# SCH.net
KiCad netlist of a schematic drawn in EasyEDA
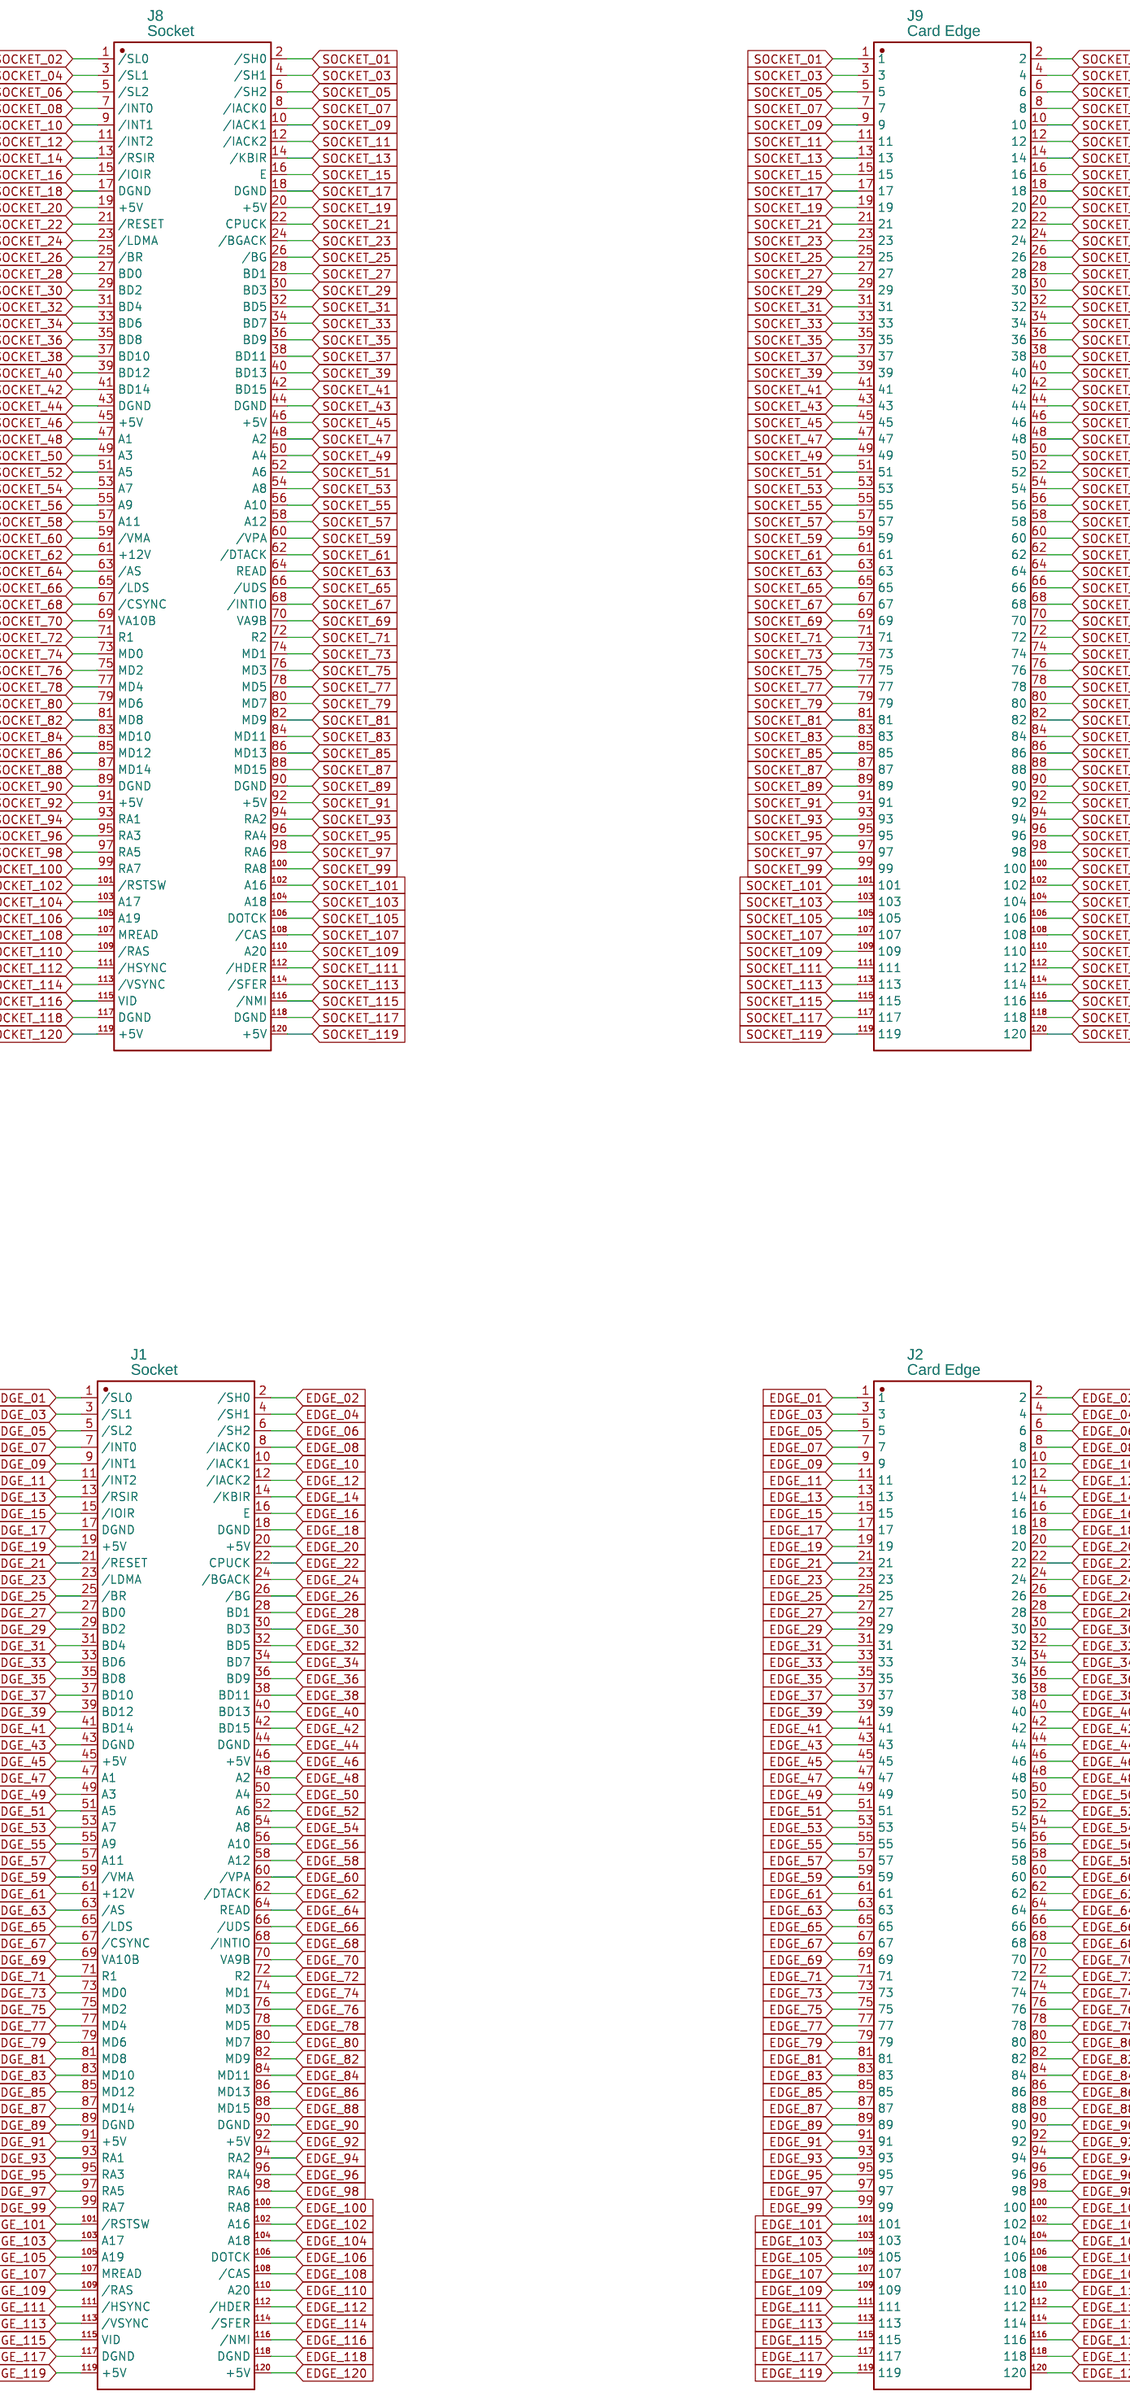
[diagram p0: schematic sheet]

(export (version "E")
  (design (tool "Eeschema 10.0.6"))
  (components
    (comp (ref "J1")
      (value "Socket")
      (fields
        (field (name "BOM_Manufacturer Part") "345-120-520-201")
        (field (name "BOM_Supplier Part") "587-345-120-520-201")
      )
      (libsource (lib "") (part "Apple Lisa 120-Pin Edge Connector_1"))
    )
    (comp (ref "J2")
      (value "Card Edge")
      (fields
        (field (name "BOM_Manufacturer Part") "345-120-520-201")
        (field (name "BOM_Supplier Part") "587-345-120-520-201")
      )
      (libsource (lib "") (part "Apple Lisa 120-Pin Edge Connector"))
    )
    (comp (ref "J8")
      (value "Socket")
      (fields
        (field (name "BOM_Manufacturer Part") "345-120-520-201")
        (field (name "BOM_Supplier Part") "587-345-120-520-201")
      )
      (libsource (lib "") (part "Apple Lisa 120-Pin Edge Connector_1"))
    )
    (comp (ref "J9")
      (value "Card Edge")
      (fields
        (field (name "BOM_Manufacturer Part") "345-120-520-201")
        (field (name "BOM_Supplier Part") "587-345-120-520-201")
      )
      (libsource (lib "") (part "Apple Lisa 120-Pin Edge Connector"))
    )
  )
  (nets
    (net (code "1") (name "EDGE_01") (class "Default")
      (node (ref "J1") (pin "1") (pinfunction "/SL0_1") (pintype "unspecified"))
      (node (ref "J2") (pin "1") (pinfunction "1_1") (pintype "unspecified"))
    )
    (net (code "2") (name "EDGE_02") (class "Default")
      (node (ref "J1") (pin "2") (pinfunction "/SH0_2") (pintype "unspecified"))
      (node (ref "J2") (pin "2") (pinfunction "2_2") (pintype "unspecified"))
    )
    (net (code "3") (name "EDGE_03") (class "Default")
      (node (ref "J1") (pin "3") (pinfunction "/SL1_3") (pintype "unspecified"))
      (node (ref "J2") (pin "3") (pinfunction "3_3") (pintype "unspecified"))
    )
    (net (code "4") (name "EDGE_04") (class "Default")
      (node (ref "J1") (pin "4") (pinfunction "/SH1_4") (pintype "unspecified"))
      (node (ref "J2") (pin "4") (pinfunction "4_4") (pintype "unspecified"))
    )
    (net (code "5") (name "EDGE_05") (class "Default")
      (node (ref "J1") (pin "5") (pinfunction "/SL2_5") (pintype "unspecified"))
      (node (ref "J2") (pin "5") (pinfunction "5_5") (pintype "unspecified"))
    )
    (net (code "6") (name "EDGE_06") (class "Default")
      (node (ref "J1") (pin "6") (pinfunction "/SH2_6") (pintype "unspecified"))
      (node (ref "J2") (pin "6") (pinfunction "6_6") (pintype "unspecified"))
    )
    (net (code "7") (name "EDGE_07") (class "Default")
      (node (ref "J1") (pin "7") (pinfunction "/INT0_7") (pintype "unspecified"))
      (node (ref "J2") (pin "7") (pinfunction "7_7") (pintype "unspecified"))
    )
    (net (code "8") (name "EDGE_08") (class "Default")
      (node (ref "J1") (pin "8") (pinfunction "/IACK0_8") (pintype "unspecified"))
      (node (ref "J2") (pin "8") (pinfunction "8_8") (pintype "unspecified"))
    )
    (net (code "9") (name "EDGE_09") (class "Default")
      (node (ref "J1") (pin "9") (pinfunction "/INT1_9") (pintype "unspecified"))
      (node (ref "J2") (pin "9") (pinfunction "9_9") (pintype "unspecified"))
    )
    (net (code "10") (name "EDGE_10") (class "Default")
      (node (ref "J1") (pin "10") (pinfunction "/IACK1_10") (pintype "unspecified"))
      (node (ref "J2") (pin "10") (pinfunction "10_10") (pintype "unspecified"))
    )
    (net (code "11") (name "EDGE_11") (class "Default")
      (node (ref "J1") (pin "11") (pinfunction "/INT2_11") (pintype "unspecified"))
      (node (ref "J2") (pin "11") (pinfunction "11_11") (pintype "unspecified"))
    )
    (net (code "12") (name "EDGE_12") (class "Default")
      (node (ref "J1") (pin "12") (pinfunction "/IACK2_12") (pintype "unspecified"))
      (node (ref "J2") (pin "12") (pinfunction "12_12") (pintype "unspecified"))
    )
    (net (code "13") (name "EDGE_13") (class "Default")
      (node (ref "J1") (pin "13") (pinfunction "/RSIR_13") (pintype "unspecified"))
      (node (ref "J2") (pin "13") (pinfunction "13_13") (pintype "unspecified"))
    )
    (net (code "14") (name "EDGE_14") (class "Default")
      (node (ref "J1") (pin "14") (pinfunction "/KBIR_14") (pintype "unspecified"))
      (node (ref "J2") (pin "14") (pinfunction "14_14") (pintype "unspecified"))
    )
    (net (code "15") (name "EDGE_15") (class "Default")
      (node (ref "J1") (pin "15") (pinfunction "/IOIR_15") (pintype "unspecified"))
      (node (ref "J2") (pin "15") (pinfunction "15_15") (pintype "unspecified"))
    )
    (net (code "16") (name "EDGE_16") (class "Default")
      (node (ref "J1") (pin "16") (pinfunction "E_16") (pintype "unspecified"))
      (node (ref "J2") (pin "16") (pinfunction "16_16") (pintype "unspecified"))
    )
    (net (code "17") (name "EDGE_17") (class "Default")
      (node (ref "J1") (pin "17") (pinfunction "DGND_17") (pintype "unspecified"))
      (node (ref "J2") (pin "17") (pinfunction "17_17") (pintype "unspecified"))
    )
    (net (code "18") (name "EDGE_18") (class "Default")
      (node (ref "J1") (pin "18") (pinfunction "DGND_18") (pintype "unspecified"))
      (node (ref "J2") (pin "18") (pinfunction "18_18") (pintype "unspecified"))
    )
    (net (code "19") (name "EDGE_19") (class "Default")
      (node (ref "J1") (pin "19") (pinfunction "+5V_19") (pintype "unspecified"))
      (node (ref "J2") (pin "19") (pinfunction "19_19") (pintype "unspecified"))
    )
    (net (code "20") (name "EDGE_20") (class "Default")
      (node (ref "J1") (pin "20") (pinfunction "+5V_20") (pintype "unspecified"))
      (node (ref "J2") (pin "20") (pinfunction "20_20") (pintype "unspecified"))
    )
    (net (code "21") (name "EDGE_21") (class "Default")
      (node (ref "J1") (pin "21") (pinfunction "/RESET_21") (pintype "unspecified"))
      (node (ref "J2") (pin "21") (pinfunction "21_21") (pintype "unspecified"))
    )
    (net (code "22") (name "EDGE_22") (class "Default")
      (node (ref "J1") (pin "22") (pinfunction "CPUCK_22") (pintype "unspecified"))
      (node (ref "J2") (pin "22") (pinfunction "22_22") (pintype "unspecified"))
    )
    (net (code "23") (name "EDGE_23") (class "Default")
      (node (ref "J1") (pin "23") (pinfunction "/LDMA_23") (pintype "unspecified"))
      (node (ref "J2") (pin "23") (pinfunction "23_23") (pintype "unspecified"))
    )
    (net (code "24") (name "EDGE_24") (class "Default")
      (node (ref "J1") (pin "24") (pinfunction "/BGACK_24") (pintype "unspecified"))
      (node (ref "J2") (pin "24") (pinfunction "24_24") (pintype "unspecified"))
    )
    (net (code "25") (name "EDGE_25") (class "Default")
      (node (ref "J1") (pin "25") (pinfunction "/BR_25") (pintype "unspecified"))
      (node (ref "J2") (pin "25") (pinfunction "25_25") (pintype "unspecified"))
    )
    (net (code "26") (name "EDGE_26") (class "Default")
      (node (ref "J1") (pin "26") (pinfunction "/BG_26") (pintype "unspecified"))
      (node (ref "J2") (pin "26") (pinfunction "26_26") (pintype "unspecified"))
    )
    (net (code "27") (name "EDGE_27") (class "Default")
      (node (ref "J1") (pin "27") (pinfunction "BD0_27") (pintype "unspecified"))
      (node (ref "J2") (pin "27") (pinfunction "27_27") (pintype "unspecified"))
    )
    (net (code "28") (name "EDGE_28") (class "Default")
      (node (ref "J1") (pin "28") (pinfunction "BD1_28") (pintype "unspecified"))
      (node (ref "J2") (pin "28") (pinfunction "28_28") (pintype "unspecified"))
    )
    (net (code "29") (name "EDGE_29") (class "Default")
      (node (ref "J1") (pin "29") (pinfunction "BD2_29") (pintype "unspecified"))
      (node (ref "J2") (pin "29") (pinfunction "29_29") (pintype "unspecified"))
    )
    (net (code "30") (name "EDGE_30") (class "Default")
      (node (ref "J1") (pin "30") (pinfunction "BD3_30") (pintype "unspecified"))
      (node (ref "J2") (pin "30") (pinfunction "30_30") (pintype "unspecified"))
    )
    (net (code "31") (name "EDGE_31") (class "Default")
      (node (ref "J1") (pin "31") (pinfunction "BD4_31") (pintype "unspecified"))
      (node (ref "J2") (pin "31") (pinfunction "31_31") (pintype "unspecified"))
    )
    (net (code "32") (name "EDGE_32") (class "Default")
      (node (ref "J1") (pin "32") (pinfunction "BD5_32") (pintype "unspecified"))
      (node (ref "J2") (pin "32") (pinfunction "32_32") (pintype "unspecified"))
    )
    (net (code "33") (name "EDGE_33") (class "Default")
      (node (ref "J1") (pin "33") (pinfunction "BD6_33") (pintype "unspecified"))
      (node (ref "J2") (pin "33") (pinfunction "33_33") (pintype "unspecified"))
    )
    (net (code "34") (name "EDGE_34") (class "Default")
      (node (ref "J1") (pin "34") (pinfunction "BD7_34") (pintype "unspecified"))
      (node (ref "J2") (pin "34") (pinfunction "34_34") (pintype "unspecified"))
    )
    (net (code "35") (name "EDGE_35") (class "Default")
      (node (ref "J1") (pin "35") (pinfunction "BD8_35") (pintype "unspecified"))
      (node (ref "J2") (pin "35") (pinfunction "35_35") (pintype "unspecified"))
    )
    (net (code "36") (name "EDGE_36") (class "Default")
      (node (ref "J1") (pin "36") (pinfunction "BD9_36") (pintype "unspecified"))
      (node (ref "J2") (pin "36") (pinfunction "36_36") (pintype "unspecified"))
    )
    (net (code "37") (name "EDGE_37") (class "Default")
      (node (ref "J1") (pin "37") (pinfunction "BD10_37") (pintype "unspecified"))
      (node (ref "J2") (pin "37") (pinfunction "37_37") (pintype "unspecified"))
    )
    (net (code "38") (name "EDGE_38") (class "Default")
      (node (ref "J1") (pin "38") (pinfunction "BD11_38") (pintype "unspecified"))
      (node (ref "J2") (pin "38") (pinfunction "38_38") (pintype "unspecified"))
    )
    (net (code "39") (name "EDGE_39") (class "Default")
      (node (ref "J1") (pin "39") (pinfunction "BD12_39") (pintype "unspecified"))
      (node (ref "J2") (pin "39") (pinfunction "39_39") (pintype "unspecified"))
    )
    (net (code "40") (name "EDGE_40") (class "Default")
      (node (ref "J1") (pin "40") (pinfunction "BD13_40") (pintype "unspecified"))
      (node (ref "J2") (pin "40") (pinfunction "40_40") (pintype "unspecified"))
    )
    (net (code "41") (name "EDGE_41") (class "Default")
      (node (ref "J1") (pin "41") (pinfunction "BD14_41") (pintype "unspecified"))
      (node (ref "J2") (pin "41") (pinfunction "41_41") (pintype "unspecified"))
    )
    (net (code "42") (name "EDGE_42") (class "Default")
      (node (ref "J1") (pin "42") (pinfunction "BD15_42") (pintype "unspecified"))
      (node (ref "J2") (pin "42") (pinfunction "42_42") (pintype "unspecified"))
    )
    (net (code "43") (name "EDGE_43") (class "Default")
      (node (ref "J1") (pin "43") (pinfunction "DGND_43") (pintype "unspecified"))
      (node (ref "J2") (pin "43") (pinfunction "43_43") (pintype "unspecified"))
    )
    (net (code "44") (name "EDGE_44") (class "Default")
      (node (ref "J1") (pin "44") (pinfunction "DGND_44") (pintype "unspecified"))
      (node (ref "J2") (pin "44") (pinfunction "44_44") (pintype "unspecified"))
    )
    (net (code "45") (name "EDGE_45") (class "Default")
      (node (ref "J1") (pin "45") (pinfunction "+5V_45") (pintype "unspecified"))
      (node (ref "J2") (pin "45") (pinfunction "45_45") (pintype "unspecified"))
    )
    (net (code "46") (name "EDGE_46") (class "Default")
      (node (ref "J1") (pin "46") (pinfunction "+5V_46") (pintype "unspecified"))
      (node (ref "J2") (pin "46") (pinfunction "46_46") (pintype "unspecified"))
    )
    (net (code "47") (name "EDGE_47") (class "Default")
      (node (ref "J1") (pin "47") (pinfunction "A1_47") (pintype "unspecified"))
      (node (ref "J2") (pin "47") (pinfunction "47_47") (pintype "unspecified"))
    )
    (net (code "48") (name "EDGE_48") (class "Default")
      (node (ref "J1") (pin "48") (pinfunction "A2_48") (pintype "unspecified"))
      (node (ref "J2") (pin "48") (pinfunction "48_48") (pintype "unspecified"))
    )
    (net (code "49") (name "EDGE_49") (class "Default")
      (node (ref "J1") (pin "49") (pinfunction "A3_49") (pintype "unspecified"))
      (node (ref "J2") (pin "49") (pinfunction "49_49") (pintype "unspecified"))
    )
    (net (code "50") (name "EDGE_50") (class "Default")
      (node (ref "J1") (pin "50") (pinfunction "A4_50") (pintype "unspecified"))
      (node (ref "J2") (pin "50") (pinfunction "50_50") (pintype "unspecified"))
    )
    (net (code "51") (name "EDGE_51") (class "Default")
      (node (ref "J1") (pin "51") (pinfunction "A5_51") (pintype "unspecified"))
      (node (ref "J2") (pin "51") (pinfunction "51_51") (pintype "unspecified"))
    )
    (net (code "52") (name "EDGE_52") (class "Default")
      (node (ref "J1") (pin "52") (pinfunction "A6_52") (pintype "unspecified"))
      (node (ref "J2") (pin "52") (pinfunction "52_52") (pintype "unspecified"))
    )
    (net (code "53") (name "EDGE_53") (class "Default")
      (node (ref "J1") (pin "53") (pinfunction "A7_53") (pintype "unspecified"))
      (node (ref "J2") (pin "53") (pinfunction "53_53") (pintype "unspecified"))
    )
    (net (code "54") (name "EDGE_54") (class "Default")
      (node (ref "J1") (pin "54") (pinfunction "A8_54") (pintype "unspecified"))
      (node (ref "J2") (pin "54") (pinfunction "54_54") (pintype "unspecified"))
    )
    (net (code "55") (name "EDGE_55") (class "Default")
      (node (ref "J1") (pin "55") (pinfunction "A9_55") (pintype "unspecified"))
      (node (ref "J2") (pin "55") (pinfunction "55_55") (pintype "unspecified"))
    )
    (net (code "56") (name "EDGE_56") (class "Default")
      (node (ref "J1") (pin "56") (pinfunction "A10_56") (pintype "unspecified"))
      (node (ref "J2") (pin "56") (pinfunction "56_56") (pintype "unspecified"))
    )
    (net (code "57") (name "EDGE_57") (class "Default")
      (node (ref "J1") (pin "57") (pinfunction "A11_57") (pintype "unspecified"))
      (node (ref "J2") (pin "57") (pinfunction "57_57") (pintype "unspecified"))
    )
    (net (code "58") (name "EDGE_58") (class "Default")
      (node (ref "J1") (pin "58") (pinfunction "A12_58") (pintype "unspecified"))
      (node (ref "J2") (pin "58") (pinfunction "58_58") (pintype "unspecified"))
    )
    (net (code "59") (name "EDGE_59") (class "Default")
      (node (ref "J1") (pin "59") (pinfunction "/VMA_59") (pintype "unspecified"))
      (node (ref "J2") (pin "59") (pinfunction "59_59") (pintype "unspecified"))
    )
    (net (code "60") (name "EDGE_60") (class "Default")
      (node (ref "J1") (pin "60") (pinfunction "/VPA_60") (pintype "unspecified"))
      (node (ref "J2") (pin "60") (pinfunction "60_60") (pintype "unspecified"))
    )
    (net (code "61") (name "EDGE_61") (class "Default")
      (node (ref "J1") (pin "61") (pinfunction "+12V_61") (pintype "unspecified"))
      (node (ref "J2") (pin "61") (pinfunction "61_61") (pintype "unspecified"))
    )
    (net (code "62") (name "EDGE_62") (class "Default")
      (node (ref "J1") (pin "62") (pinfunction "/DTACK_62") (pintype "unspecified"))
      (node (ref "J2") (pin "62") (pinfunction "62_62") (pintype "unspecified"))
    )
    (net (code "63") (name "EDGE_63") (class "Default")
      (node (ref "J1") (pin "63") (pinfunction "/AS_63") (pintype "unspecified"))
      (node (ref "J2") (pin "63") (pinfunction "63_63") (pintype "unspecified"))
    )
    (net (code "64") (name "EDGE_64") (class "Default")
      (node (ref "J1") (pin "64") (pinfunction "READ_64") (pintype "unspecified"))
      (node (ref "J2") (pin "64") (pinfunction "64_64") (pintype "unspecified"))
    )
    (net (code "65") (name "EDGE_65") (class "Default")
      (node (ref "J1") (pin "65") (pinfunction "/LDS_65") (pintype "unspecified"))
      (node (ref "J2") (pin "65") (pinfunction "65_65") (pintype "unspecified"))
    )
    (net (code "66") (name "EDGE_66") (class "Default")
      (node (ref "J1") (pin "66") (pinfunction "/UDS_66") (pintype "unspecified"))
      (node (ref "J2") (pin "66") (pinfunction "66_66") (pintype "unspecified"))
    )
    (net (code "67") (name "EDGE_67") (class "Default")
      (node (ref "J1") (pin "67") (pinfunction "/CSYNC_67") (pintype "unspecified"))
      (node (ref "J2") (pin "67") (pinfunction "67_67") (pintype "unspecified"))
    )
    (net (code "68") (name "EDGE_68") (class "Default")
      (node (ref "J1") (pin "68") (pinfunction "/INTIO_68") (pintype "unspecified"))
      (node (ref "J2") (pin "68") (pinfunction "68_68") (pintype "unspecified"))
    )
    (net (code "69") (name "EDGE_69") (class "Default")
      (node (ref "J1") (pin "69") (pinfunction "VA10B_69") (pintype "unspecified"))
      (node (ref "J2") (pin "69") (pinfunction "69_69") (pintype "unspecified"))
    )
    (net (code "70") (name "EDGE_70") (class "Default")
      (node (ref "J1") (pin "70") (pinfunction "VA9B_70") (pintype "unspecified"))
      (node (ref "J2") (pin "70") (pinfunction "70_70") (pintype "unspecified"))
    )
    (net (code "71") (name "EDGE_71") (class "Default")
      (node (ref "J1") (pin "71") (pinfunction "R1_71") (pintype "unspecified"))
      (node (ref "J2") (pin "71") (pinfunction "71_71") (pintype "unspecified"))
    )
    (net (code "72") (name "EDGE_72") (class "Default")
      (node (ref "J1") (pin "72") (pinfunction "R2_72") (pintype "unspecified"))
      (node (ref "J2") (pin "72") (pinfunction "72_72") (pintype "unspecified"))
    )
    (net (code "73") (name "EDGE_73") (class "Default")
      (node (ref "J1") (pin "73") (pinfunction "MD0_73") (pintype "unspecified"))
      (node (ref "J2") (pin "73") (pinfunction "73_73") (pintype "unspecified"))
    )
    (net (code "74") (name "EDGE_74") (class "Default")
      (node (ref "J1") (pin "74") (pinfunction "MD1_74") (pintype "unspecified"))
      (node (ref "J2") (pin "74") (pinfunction "74_74") (pintype "unspecified"))
    )
    (net (code "75") (name "EDGE_75") (class "Default")
      (node (ref "J1") (pin "75") (pinfunction "MD2_75") (pintype "unspecified"))
      (node (ref "J2") (pin "75") (pinfunction "75_75") (pintype "unspecified"))
    )
    (net (code "76") (name "EDGE_76") (class "Default")
      (node (ref "J1") (pin "76") (pinfunction "MD3_76") (pintype "unspecified"))
      (node (ref "J2") (pin "76") (pinfunction "76_76") (pintype "unspecified"))
    )
    (net (code "77") (name "EDGE_77") (class "Default")
      (node (ref "J1") (pin "77") (pinfunction "MD4_77") (pintype "unspecified"))
      (node (ref "J2") (pin "77") (pinfunction "77_77") (pintype "unspecified"))
    )
    (net (code "78") (name "EDGE_78") (class "Default")
      (node (ref "J1") (pin "78") (pinfunction "MD5_78") (pintype "unspecified"))
      (node (ref "J2") (pin "78") (pinfunction "78_78") (pintype "unspecified"))
    )
    (net (code "79") (name "EDGE_79") (class "Default")
      (node (ref "J1") (pin "79") (pinfunction "MD6_79") (pintype "unspecified"))
      (node (ref "J2") (pin "79") (pinfunction "79_79") (pintype "unspecified"))
    )
    (net (code "80") (name "EDGE_80") (class "Default")
      (node (ref "J1") (pin "80") (pinfunction "MD7_80") (pintype "unspecified"))
      (node (ref "J2") (pin "80") (pinfunction "80_80") (pintype "unspecified"))
    )
    (net (code "81") (name "EDGE_81") (class "Default")
      (node (ref "J1") (pin "81") (pinfunction "MD8_81") (pintype "unspecified"))
      (node (ref "J2") (pin "81") (pinfunction "81_81") (pintype "unspecified"))
    )
    (net (code "82") (name "EDGE_82") (class "Default")
      (node (ref "J1") (pin "82") (pinfunction "MD9_82") (pintype "unspecified"))
      (node (ref "J2") (pin "82") (pinfunction "82_82") (pintype "unspecified"))
    )
    (net (code "83") (name "EDGE_83") (class "Default")
      (node (ref "J1") (pin "83") (pinfunction "MD10_83") (pintype "unspecified"))
      (node (ref "J2") (pin "83") (pinfunction "83_83") (pintype "unspecified"))
    )
    (net (code "84") (name "EDGE_84") (class "Default")
      (node (ref "J1") (pin "84") (pinfunction "MD11_84") (pintype "unspecified"))
      (node (ref "J2") (pin "84") (pinfunction "84_84") (pintype "unspecified"))
    )
    (net (code "85") (name "EDGE_85") (class "Default")
      (node (ref "J1") (pin "85") (pinfunction "MD12_85") (pintype "unspecified"))
      (node (ref "J2") (pin "85") (pinfunction "85_85") (pintype "unspecified"))
    )
    (net (code "86") (name "EDGE_86") (class "Default")
      (node (ref "J1") (pin "86") (pinfunction "MD13_86") (pintype "unspecified"))
      (node (ref "J2") (pin "86") (pinfunction "86_86") (pintype "unspecified"))
    )
    (net (code "87") (name "EDGE_87") (class "Default")
      (node (ref "J1") (pin "87") (pinfunction "MD14_87") (pintype "unspecified"))
      (node (ref "J2") (pin "87") (pinfunction "87_87") (pintype "unspecified"))
    )
    (net (code "88") (name "EDGE_88") (class "Default")
      (node (ref "J1") (pin "88") (pinfunction "MD15_88") (pintype "unspecified"))
      (node (ref "J2") (pin "88") (pinfunction "88_88") (pintype "unspecified"))
    )
    (net (code "89") (name "EDGE_89") (class "Default")
      (node (ref "J1") (pin "89") (pinfunction "DGND_89") (pintype "unspecified"))
      (node (ref "J2") (pin "89") (pinfunction "89_89") (pintype "unspecified"))
    )
    (net (code "90") (name "EDGE_90") (class "Default")
      (node (ref "J1") (pin "90") (pinfunction "DGND_90") (pintype "unspecified"))
      (node (ref "J2") (pin "90") (pinfunction "90_90") (pintype "unspecified"))
    )
    (net (code "91") (name "EDGE_91") (class "Default")
      (node (ref "J1") (pin "91") (pinfunction "+5V_91") (pintype "unspecified"))
      (node (ref "J2") (pin "91") (pinfunction "91_91") (pintype "unspecified"))
    )
    (net (code "92") (name "EDGE_92") (class "Default")
      (node (ref "J1") (pin "92") (pinfunction "+5V_92") (pintype "unspecified"))
      (node (ref "J2") (pin "92") (pinfunction "92_92") (pintype "unspecified"))
    )
    (net (code "93") (name "EDGE_93") (class "Default")
      (node (ref "J1") (pin "93") (pinfunction "RA1_93") (pintype "unspecified"))
      (node (ref "J2") (pin "93") (pinfunction "93_93") (pintype "unspecified"))
    )
    (net (code "94") (name "EDGE_94") (class "Default")
      (node (ref "J1") (pin "94") (pinfunction "RA2_94") (pintype "unspecified"))
      (node (ref "J2") (pin "94") (pinfunction "94_94") (pintype "unspecified"))
    )
    (net (code "95") (name "EDGE_95") (class "Default")
      (node (ref "J1") (pin "95") (pinfunction "RA3_95") (pintype "unspecified"))
      (node (ref "J2") (pin "95") (pinfunction "95_95") (pintype "unspecified"))
    )
    (net (code "96") (name "EDGE_96") (class "Default")
      (node (ref "J1") (pin "96") (pinfunction "RA4_96") (pintype "unspecified"))
      (node (ref "J2") (pin "96") (pinfunction "96_96") (pintype "unspecified"))
    )
    (net (code "97") (name "EDGE_97") (class "Default")
      (node (ref "J1") (pin "97") (pinfunction "RA5_97") (pintype "unspecified"))
      (node (ref "J2") (pin "97") (pinfunction "97_97") (pintype "unspecified"))
    )
    (net (code "98") (name "EDGE_98") (class "Default")
      (node (ref "J1") (pin "98") (pinfunction "RA6_98") (pintype "unspecified"))
      (node (ref "J2") (pin "98") (pinfunction "98_98") (pintype "unspecified"))
    )
    (net (code "99") (name "EDGE_99") (class "Default")
      (node (ref "J1") (pin "99") (pinfunction "RA7_99") (pintype "unspecified"))
      (node (ref "J2") (pin "99") (pinfunction "99_99") (pintype "unspecified"))
    )
    (net (code "100") (name "EDGE_100") (class "Default")
      (node (ref "J1") (pin "100") (pinfunction "RA8_100") (pintype "unspecified"))
      (node (ref "J2") (pin "100") (pinfunction "100_100") (pintype "unspecified"))
    )
    (net (code "101") (name "EDGE_101") (class "Default")
      (node (ref "J1") (pin "101") (pinfunction "/RSTSW_101") (pintype "unspecified"))
      (node (ref "J2") (pin "101") (pinfunction "101_101") (pintype "unspecified"))
    )
    (net (code "102") (name "EDGE_102") (class "Default")
      (node (ref "J1") (pin "102") (pinfunction "A16_102") (pintype "unspecified"))
      (node (ref "J2") (pin "102") (pinfunction "102_102") (pintype "unspecified"))
    )
    (net (code "103") (name "EDGE_103") (class "Default")
      (node (ref "J1") (pin "103") (pinfunction "A17_103") (pintype "unspecified"))
      (node (ref "J2") (pin "103") (pinfunction "103_103") (pintype "unspecified"))
    )
    (net (code "104") (name "EDGE_104") (class "Default")
      (node (ref "J1") (pin "104") (pinfunction "A18_104") (pintype "unspecified"))
      (node (ref "J2") (pin "104") (pinfunction "104_104") (pintype "unspecified"))
    )
    (net (code "105") (name "EDGE_105") (class "Default")
      (node (ref "J1") (pin "105") (pinfunction "A19_105") (pintype "unspecified"))
      (node (ref "J2") (pin "105") (pinfunction "105_105") (pintype "unspecified"))
    )
    (net (code "106") (name "EDGE_106") (class "Default")
      (node (ref "J1") (pin "106") (pinfunction "DOTCK_106") (pintype "unspecified"))
      (node (ref "J2") (pin "106") (pinfunction "106_106") (pintype "unspecified"))
    )
    (net (code "107") (name "EDGE_107") (class "Default")
      (node (ref "J1") (pin "107") (pinfunction "MREAD_107") (pintype "unspecified"))
      (node (ref "J2") (pin "107") (pinfunction "107_107") (pintype "unspecified"))
    )
    (net (code "108") (name "EDGE_108") (class "Default")
      (node (ref "J1") (pin "108") (pinfunction "/CAS_108") (pintype "unspecified"))
      (node (ref "J2") (pin "108") (pinfunction "108_108") (pintype "unspecified"))
    )
    (net (code "109") (name "EDGE_109") (class "Default")
      (node (ref "J1") (pin "109") (pinfunction "/RAS_109") (pintype "unspecified"))
      (node (ref "J2") (pin "109") (pinfunction "109_109") (pintype "unspecified"))
    )
    (net (code "110") (name "EDGE_110") (class "Default")
      (node (ref "J1") (pin "110") (pinfunction "A20_110") (pintype "unspecified"))
      (node (ref "J2") (pin "110") (pinfunction "110_110") (pintype "unspecified"))
    )
    (net (code "111") (name "EDGE_111") (class "Default")
      (node (ref "J1") (pin "111") (pinfunction "/HSYNC_111") (pintype "unspecified"))
      (node (ref "J2") (pin "111") (pinfunction "111_111") (pintype "unspecified"))
    )
    (net (code "112") (name "EDGE_112") (class "Default")
      (node (ref "J1") (pin "112") (pinfunction "/HDER_112") (pintype "unspecified"))
      (node (ref "J2") (pin "112") (pinfunction "112_112") (pintype "unspecified"))
    )
    (net (code "113") (name "EDGE_113") (class "Default")
      (node (ref "J1") (pin "113") (pinfunction "/VSYNC_113") (pintype "unspecified"))
      (node (ref "J2") (pin "113") (pinfunction "113_113") (pintype "unspecified"))
    )
    (net (code "114") (name "EDGE_114") (class "Default")
      (node (ref "J1") (pin "114") (pinfunction "/SFER_114") (pintype "unspecified"))
      (node (ref "J2") (pin "114") (pinfunction "114_114") (pintype "unspecified"))
    )
    (net (code "115") (name "EDGE_115") (class "Default")
      (node (ref "J1") (pin "115") (pinfunction "VID_115") (pintype "unspecified"))
      (node (ref "J2") (pin "115") (pinfunction "115_115") (pintype "unspecified"))
    )
    (net (code "116") (name "EDGE_116") (class "Default")
      (node (ref "J1") (pin "116") (pinfunction "/NMI_116") (pintype "unspecified"))
      (node (ref "J2") (pin "116") (pinfunction "116_116") (pintype "unspecified"))
    )
    (net (code "117") (name "EDGE_117") (class "Default")
      (node (ref "J1") (pin "117") (pinfunction "DGND_117") (pintype "unspecified"))
      (node (ref "J2") (pin "117") (pinfunction "117_117") (pintype "unspecified"))
    )
    (net (code "118") (name "EDGE_118") (class "Default")
      (node (ref "J1") (pin "118") (pinfunction "DGND_118") (pintype "unspecified"))
      (node (ref "J2") (pin "118") (pinfunction "118_118") (pintype "unspecified"))
    )
    (net (code "119") (name "EDGE_119") (class "Default")
      (node (ref "J1") (pin "119") (pinfunction "+5V_119") (pintype "unspecified"))
      (node (ref "J2") (pin "119") (pinfunction "119_119") (pintype "unspecified"))
    )
    (net (code "120") (name "EDGE_120") (class "Default")
      (node (ref "J1") (pin "120") (pinfunction "+5V_120") (pintype "unspecified"))
      (node (ref "J2") (pin "120") (pinfunction "120_120") (pintype "unspecified"))
    )
    (net (code "121") (name "SOCKET_01") (class "Default")
      (node (ref "J8") (pin "2") (pinfunction "/SH0_2") (pintype "unspecified"))
      (node (ref "J9") (pin "1") (pinfunction "1_1") (pintype "unspecified"))
    )
    (net (code "122") (name "SOCKET_02") (class "Default")
      (node (ref "J8") (pin "1") (pinfunction "/SL0_1") (pintype "unspecified"))
      (node (ref "J9") (pin "2") (pinfunction "2_2") (pintype "unspecified"))
    )
    (net (code "123") (name "SOCKET_03") (class "Default")
      (node (ref "J8") (pin "4") (pinfunction "/SH1_4") (pintype "unspecified"))
      (node (ref "J9") (pin "3") (pinfunction "3_3") (pintype "unspecified"))
    )
    (net (code "124") (name "SOCKET_04") (class "Default")
      (node (ref "J8") (pin "3") (pinfunction "/SL1_3") (pintype "unspecified"))
      (node (ref "J9") (pin "4") (pinfunction "4_4") (pintype "unspecified"))
    )
    (net (code "125") (name "SOCKET_05") (class "Default")
      (node (ref "J8") (pin "6") (pinfunction "/SH2_6") (pintype "unspecified"))
      (node (ref "J9") (pin "5") (pinfunction "5_5") (pintype "unspecified"))
    )
    (net (code "126") (name "SOCKET_06") (class "Default")
      (node (ref "J8") (pin "5") (pinfunction "/SL2_5") (pintype "unspecified"))
      (node (ref "J9") (pin "6") (pinfunction "6_6") (pintype "unspecified"))
    )
    (net (code "127") (name "SOCKET_07") (class "Default")
      (node (ref "J8") (pin "8") (pinfunction "/IACK0_8") (pintype "unspecified"))
      (node (ref "J9") (pin "7") (pinfunction "7_7") (pintype "unspecified"))
    )
    (net (code "128") (name "SOCKET_08") (class "Default")
      (node (ref "J8") (pin "7") (pinfunction "/INT0_7") (pintype "unspecified"))
      (node (ref "J9") (pin "8") (pinfunction "8_8") (pintype "unspecified"))
    )
    (net (code "129") (name "SOCKET_09") (class "Default")
      (node (ref "J8") (pin "10") (pinfunction "/IACK1_10") (pintype "unspecified"))
      (node (ref "J9") (pin "9") (pinfunction "9_9") (pintype "unspecified"))
    )
    (net (code "130") (name "SOCKET_10") (class "Default")
      (node (ref "J8") (pin "9") (pinfunction "/INT1_9") (pintype "unspecified"))
      (node (ref "J9") (pin "10") (pinfunction "10_10") (pintype "unspecified"))
    )
    (net (code "131") (name "SOCKET_11") (class "Default")
      (node (ref "J8") (pin "12") (pinfunction "/IACK2_12") (pintype "unspecified"))
      (node (ref "J9") (pin "11") (pinfunction "11_11") (pintype "unspecified"))
    )
    (net (code "132") (name "SOCKET_12") (class "Default")
      (node (ref "J8") (pin "11") (pinfunction "/INT2_11") (pintype "unspecified"))
      (node (ref "J9") (pin "12") (pinfunction "12_12") (pintype "unspecified"))
    )
    (net (code "133") (name "SOCKET_13") (class "Default")
      (node (ref "J8") (pin "14") (pinfunction "/KBIR_14") (pintype "unspecified"))
      (node (ref "J9") (pin "13") (pinfunction "13_13") (pintype "unspecified"))
    )
    (net (code "134") (name "SOCKET_14") (class "Default")
      (node (ref "J8") (pin "13") (pinfunction "/RSIR_13") (pintype "unspecified"))
      (node (ref "J9") (pin "14") (pinfunction "14_14") (pintype "unspecified"))
    )
    (net (code "135") (name "SOCKET_15") (class "Default")
      (node (ref "J8") (pin "16") (pinfunction "E_16") (pintype "unspecified"))
      (node (ref "J9") (pin "15") (pinfunction "15_15") (pintype "unspecified"))
    )
    (net (code "136") (name "SOCKET_16") (class "Default")
      (node (ref "J8") (pin "15") (pinfunction "/IOIR_15") (pintype "unspecified"))
      (node (ref "J9") (pin "16") (pinfunction "16_16") (pintype "unspecified"))
    )
    (net (code "137") (name "SOCKET_17") (class "Default")
      (node (ref "J8") (pin "18") (pinfunction "DGND_18") (pintype "unspecified"))
      (node (ref "J9") (pin "17") (pinfunction "17_17") (pintype "unspecified"))
    )
    (net (code "138") (name "SOCKET_18") (class "Default")
      (node (ref "J8") (pin "17") (pinfunction "DGND_17") (pintype "unspecified"))
      (node (ref "J9") (pin "18") (pinfunction "18_18") (pintype "unspecified"))
    )
    (net (code "139") (name "SOCKET_19") (class "Default")
      (node (ref "J8") (pin "20") (pinfunction "+5V_20") (pintype "unspecified"))
      (node (ref "J9") (pin "19") (pinfunction "19_19") (pintype "unspecified"))
    )
    (net (code "140") (name "SOCKET_20") (class "Default")
      (node (ref "J8") (pin "19") (pinfunction "+5V_19") (pintype "unspecified"))
      (node (ref "J9") (pin "20") (pinfunction "20_20") (pintype "unspecified"))
    )
    (net (code "141") (name "SOCKET_21") (class "Default")
      (node (ref "J8") (pin "22") (pinfunction "CPUCK_22") (pintype "unspecified"))
      (node (ref "J9") (pin "21") (pinfunction "21_21") (pintype "unspecified"))
    )
    (net (code "142") (name "SOCKET_22") (class "Default")
      (node (ref "J8") (pin "21") (pinfunction "/RESET_21") (pintype "unspecified"))
      (node (ref "J9") (pin "22") (pinfunction "22_22") (pintype "unspecified"))
    )
    (net (code "143") (name "SOCKET_23") (class "Default")
      (node (ref "J8") (pin "24") (pinfunction "/BGACK_24") (pintype "unspecified"))
      (node (ref "J9") (pin "23") (pinfunction "23_23") (pintype "unspecified"))
    )
    (net (code "144") (name "SOCKET_24") (class "Default")
      (node (ref "J8") (pin "23") (pinfunction "/LDMA_23") (pintype "unspecified"))
      (node (ref "J9") (pin "24") (pinfunction "24_24") (pintype "unspecified"))
    )
    (net (code "145") (name "SOCKET_25") (class "Default")
      (node (ref "J8") (pin "26") (pinfunction "/BG_26") (pintype "unspecified"))
      (node (ref "J9") (pin "25") (pinfunction "25_25") (pintype "unspecified"))
    )
    (net (code "146") (name "SOCKET_26") (class "Default")
      (node (ref "J8") (pin "25") (pinfunction "/BR_25") (pintype "unspecified"))
      (node (ref "J9") (pin "26") (pinfunction "26_26") (pintype "unspecified"))
    )
    (net (code "147") (name "SOCKET_27") (class "Default")
      (node (ref "J8") (pin "28") (pinfunction "BD1_28") (pintype "unspecified"))
      (node (ref "J9") (pin "27") (pinfunction "27_27") (pintype "unspecified"))
    )
    (net (code "148") (name "SOCKET_28") (class "Default")
      (node (ref "J8") (pin "27") (pinfunction "BD0_27") (pintype "unspecified"))
      (node (ref "J9") (pin "28") (pinfunction "28_28") (pintype "unspecified"))
    )
    (net (code "149") (name "SOCKET_29") (class "Default")
      (node (ref "J8") (pin "30") (pinfunction "BD3_30") (pintype "unspecified"))
      (node (ref "J9") (pin "29") (pinfunction "29_29") (pintype "unspecified"))
    )
    (net (code "150") (name "SOCKET_30") (class "Default")
      (node (ref "J8") (pin "29") (pinfunction "BD2_29") (pintype "unspecified"))
      (node (ref "J9") (pin "30") (pinfunction "30_30") (pintype "unspecified"))
    )
    (net (code "151") (name "SOCKET_31") (class "Default")
      (node (ref "J8") (pin "32") (pinfunction "BD5_32") (pintype "unspecified"))
      (node (ref "J9") (pin "31") (pinfunction "31_31") (pintype "unspecified"))
    )
    (net (code "152") (name "SOCKET_32") (class "Default")
      (node (ref "J8") (pin "31") (pinfunction "BD4_31") (pintype "unspecified"))
      (node (ref "J9") (pin "32") (pinfunction "32_32") (pintype "unspecified"))
    )
    (net (code "153") (name "SOCKET_33") (class "Default")
      (node (ref "J8") (pin "34") (pinfunction "BD7_34") (pintype "unspecified"))
      (node (ref "J9") (pin "33") (pinfunction "33_33") (pintype "unspecified"))
    )
    (net (code "154") (name "SOCKET_34") (class "Default")
      (node (ref "J8") (pin "33") (pinfunction "BD6_33") (pintype "unspecified"))
      (node (ref "J9") (pin "34") (pinfunction "34_34") (pintype "unspecified"))
    )
    (net (code "155") (name "SOCKET_35") (class "Default")
      (node (ref "J8") (pin "36") (pinfunction "BD9_36") (pintype "unspecified"))
      (node (ref "J9") (pin "35") (pinfunction "35_35") (pintype "unspecified"))
    )
    (net (code "156") (name "SOCKET_36") (class "Default")
      (node (ref "J8") (pin "35") (pinfunction "BD8_35") (pintype "unspecified"))
      (node (ref "J9") (pin "36") (pinfunction "36_36") (pintype "unspecified"))
    )
    (net (code "157") (name "SOCKET_37") (class "Default")
      (node (ref "J8") (pin "38") (pinfunction "BD11_38") (pintype "unspecified"))
      (node (ref "J9") (pin "37") (pinfunction "37_37") (pintype "unspecified"))
    )
    (net (code "158") (name "SOCKET_38") (class "Default")
      (node (ref "J8") (pin "37") (pinfunction "BD10_37") (pintype "unspecified"))
      (node (ref "J9") (pin "38") (pinfunction "38_38") (pintype "unspecified"))
    )
    (net (code "159") (name "SOCKET_39") (class "Default")
      (node (ref "J8") (pin "40") (pinfunction "BD13_40") (pintype "unspecified"))
      (node (ref "J9") (pin "39") (pinfunction "39_39") (pintype "unspecified"))
    )
    (net (code "160") (name "SOCKET_40") (class "Default")
      (node (ref "J8") (pin "39") (pinfunction "BD12_39") (pintype "unspecified"))
      (node (ref "J9") (pin "40") (pinfunction "40_40") (pintype "unspecified"))
    )
    (net (code "161") (name "SOCKET_41") (class "Default")
      (node (ref "J8") (pin "42") (pinfunction "BD15_42") (pintype "unspecified"))
      (node (ref "J9") (pin "41") (pinfunction "41_41") (pintype "unspecified"))
    )
    (net (code "162") (name "SOCKET_42") (class "Default")
      (node (ref "J8") (pin "41") (pinfunction "BD14_41") (pintype "unspecified"))
      (node (ref "J9") (pin "42") (pinfunction "42_42") (pintype "unspecified"))
    )
    (net (code "163") (name "SOCKET_43") (class "Default")
      (node (ref "J8") (pin "44") (pinfunction "DGND_44") (pintype "unspecified"))
      (node (ref "J9") (pin "43") (pinfunction "43_43") (pintype "unspecified"))
    )
    (net (code "164") (name "SOCKET_44") (class "Default")
      (node (ref "J8") (pin "43") (pinfunction "DGND_43") (pintype "unspecified"))
      (node (ref "J9") (pin "44") (pinfunction "44_44") (pintype "unspecified"))
    )
    (net (code "165") (name "SOCKET_45") (class "Default")
      (node (ref "J8") (pin "46") (pinfunction "+5V_46") (pintype "unspecified"))
      (node (ref "J9") (pin "45") (pinfunction "45_45") (pintype "unspecified"))
    )
    (net (code "166") (name "SOCKET_46") (class "Default")
      (node (ref "J8") (pin "45") (pinfunction "+5V_45") (pintype "unspecified"))
      (node (ref "J9") (pin "46") (pinfunction "46_46") (pintype "unspecified"))
    )
    (net (code "167") (name "SOCKET_47") (class "Default")
      (node (ref "J8") (pin "48") (pinfunction "A2_48") (pintype "unspecified"))
      (node (ref "J9") (pin "47") (pinfunction "47_47") (pintype "unspecified"))
    )
    (net (code "168") (name "SOCKET_48") (class "Default")
      (node (ref "J8") (pin "47") (pinfunction "A1_47") (pintype "unspecified"))
      (node (ref "J9") (pin "48") (pinfunction "48_48") (pintype "unspecified"))
    )
    (net (code "169") (name "SOCKET_49") (class "Default")
      (node (ref "J8") (pin "50") (pinfunction "A4_50") (pintype "unspecified"))
      (node (ref "J9") (pin "49") (pinfunction "49_49") (pintype "unspecified"))
    )
    (net (code "170") (name "SOCKET_50") (class "Default")
      (node (ref "J8") (pin "49") (pinfunction "A3_49") (pintype "unspecified"))
      (node (ref "J9") (pin "50") (pinfunction "50_50") (pintype "unspecified"))
    )
    (net (code "171") (name "SOCKET_51") (class "Default")
      (node (ref "J8") (pin "52") (pinfunction "A6_52") (pintype "unspecified"))
      (node (ref "J9") (pin "51") (pinfunction "51_51") (pintype "unspecified"))
    )
    (net (code "172") (name "SOCKET_52") (class "Default")
      (node (ref "J8") (pin "51") (pinfunction "A5_51") (pintype "unspecified"))
      (node (ref "J9") (pin "52") (pinfunction "52_52") (pintype "unspecified"))
    )
    (net (code "173") (name "SOCKET_53") (class "Default")
      (node (ref "J8") (pin "54") (pinfunction "A8_54") (pintype "unspecified"))
      (node (ref "J9") (pin "53") (pinfunction "53_53") (pintype "unspecified"))
    )
    (net (code "174") (name "SOCKET_54") (class "Default")
      (node (ref "J8") (pin "53") (pinfunction "A7_53") (pintype "unspecified"))
      (node (ref "J9") (pin "54") (pinfunction "54_54") (pintype "unspecified"))
    )
    (net (code "175") (name "SOCKET_55") (class "Default")
      (node (ref "J8") (pin "56") (pinfunction "A10_56") (pintype "unspecified"))
      (node (ref "J9") (pin "55") (pinfunction "55_55") (pintype "unspecified"))
    )
    (net (code "176") (name "SOCKET_56") (class "Default")
      (node (ref "J8") (pin "55") (pinfunction "A9_55") (pintype "unspecified"))
      (node (ref "J9") (pin "56") (pinfunction "56_56") (pintype "unspecified"))
    )
    (net (code "177") (name "SOCKET_57") (class "Default")
      (node (ref "J8") (pin "58") (pinfunction "A12_58") (pintype "unspecified"))
      (node (ref "J9") (pin "57") (pinfunction "57_57") (pintype "unspecified"))
    )
    (net (code "178") (name "SOCKET_58") (class "Default")
      (node (ref "J8") (pin "57") (pinfunction "A11_57") (pintype "unspecified"))
      (node (ref "J9") (pin "58") (pinfunction "58_58") (pintype "unspecified"))
    )
    (net (code "179") (name "SOCKET_59") (class "Default")
      (node (ref "J8") (pin "60") (pinfunction "/VPA_60") (pintype "unspecified"))
      (node (ref "J9") (pin "59") (pinfunction "59_59") (pintype "unspecified"))
    )
    (net (code "180") (name "SOCKET_60") (class "Default")
      (node (ref "J8") (pin "59") (pinfunction "/VMA_59") (pintype "unspecified"))
      (node (ref "J9") (pin "60") (pinfunction "60_60") (pintype "unspecified"))
    )
    (net (code "181") (name "SOCKET_61") (class "Default")
      (node (ref "J8") (pin "62") (pinfunction "/DTACK_62") (pintype "unspecified"))
      (node (ref "J9") (pin "61") (pinfunction "61_61") (pintype "unspecified"))
    )
    (net (code "182") (name "SOCKET_62") (class "Default")
      (node (ref "J8") (pin "61") (pinfunction "+12V_61") (pintype "unspecified"))
      (node (ref "J9") (pin "62") (pinfunction "62_62") (pintype "unspecified"))
    )
    (net (code "183") (name "SOCKET_63") (class "Default")
      (node (ref "J8") (pin "64") (pinfunction "READ_64") (pintype "unspecified"))
      (node (ref "J9") (pin "63") (pinfunction "63_63") (pintype "unspecified"))
    )
    (net (code "184") (name "SOCKET_64") (class "Default")
      (node (ref "J8") (pin "63") (pinfunction "/AS_63") (pintype "unspecified"))
      (node (ref "J9") (pin "64") (pinfunction "64_64") (pintype "unspecified"))
    )
    (net (code "185") (name "SOCKET_65") (class "Default")
      (node (ref "J8") (pin "66") (pinfunction "/UDS_66") (pintype "unspecified"))
      (node (ref "J9") (pin "65") (pinfunction "65_65") (pintype "unspecified"))
    )
    (net (code "186") (name "SOCKET_66") (class "Default")
      (node (ref "J8") (pin "65") (pinfunction "/LDS_65") (pintype "unspecified"))
      (node (ref "J9") (pin "66") (pinfunction "66_66") (pintype "unspecified"))
    )
    (net (code "187") (name "SOCKET_67") (class "Default")
      (node (ref "J8") (pin "68") (pinfunction "/INTIO_68") (pintype "unspecified"))
      (node (ref "J9") (pin "67") (pinfunction "67_67") (pintype "unspecified"))
    )
    (net (code "188") (name "SOCKET_68") (class "Default")
      (node (ref "J8") (pin "67") (pinfunction "/CSYNC_67") (pintype "unspecified"))
      (node (ref "J9") (pin "68") (pinfunction "68_68") (pintype "unspecified"))
    )
    (net (code "189") (name "SOCKET_69") (class "Default")
      (node (ref "J8") (pin "70") (pinfunction "VA9B_70") (pintype "unspecified"))
      (node (ref "J9") (pin "69") (pinfunction "69_69") (pintype "unspecified"))
    )
    (net (code "190") (name "SOCKET_70") (class "Default")
      (node (ref "J8") (pin "69") (pinfunction "VA10B_69") (pintype "unspecified"))
      (node (ref "J9") (pin "70") (pinfunction "70_70") (pintype "unspecified"))
    )
    (net (code "191") (name "SOCKET_71") (class "Default")
      (node (ref "J8") (pin "72") (pinfunction "R2_72") (pintype "unspecified"))
      (node (ref "J9") (pin "71") (pinfunction "71_71") (pintype "unspecified"))
    )
    (net (code "192") (name "SOCKET_72") (class "Default")
      (node (ref "J8") (pin "71") (pinfunction "R1_71") (pintype "unspecified"))
      (node (ref "J9") (pin "72") (pinfunction "72_72") (pintype "unspecified"))
    )
    (net (code "193") (name "SOCKET_73") (class "Default")
      (node (ref "J8") (pin "74") (pinfunction "MD1_74") (pintype "unspecified"))
      (node (ref "J9") (pin "73") (pinfunction "73_73") (pintype "unspecified"))
    )
    (net (code "194") (name "SOCKET_74") (class "Default")
      (node (ref "J8") (pin "73") (pinfunction "MD0_73") (pintype "unspecified"))
      (node (ref "J9") (pin "74") (pinfunction "74_74") (pintype "unspecified"))
    )
    (net (code "195") (name "SOCKET_75") (class "Default")
      (node (ref "J8") (pin "76") (pinfunction "MD3_76") (pintype "unspecified"))
      (node (ref "J9") (pin "75") (pinfunction "75_75") (pintype "unspecified"))
    )
    (net (code "196") (name "SOCKET_76") (class "Default")
      (node (ref "J8") (pin "75") (pinfunction "MD2_75") (pintype "unspecified"))
      (node (ref "J9") (pin "76") (pinfunction "76_76") (pintype "unspecified"))
    )
    (net (code "197") (name "SOCKET_77") (class "Default")
      (node (ref "J8") (pin "78") (pinfunction "MD5_78") (pintype "unspecified"))
      (node (ref "J9") (pin "77") (pinfunction "77_77") (pintype "unspecified"))
    )
    (net (code "198") (name "SOCKET_78") (class "Default")
      (node (ref "J8") (pin "77") (pinfunction "MD4_77") (pintype "unspecified"))
      (node (ref "J9") (pin "78") (pinfunction "78_78") (pintype "unspecified"))
    )
    (net (code "199") (name "SOCKET_79") (class "Default")
      (node (ref "J8") (pin "80") (pinfunction "MD7_80") (pintype "unspecified"))
      (node (ref "J9") (pin "79") (pinfunction "79_79") (pintype "unspecified"))
    )
    (net (code "200") (name "SOCKET_80") (class "Default")
      (node (ref "J8") (pin "79") (pinfunction "MD6_79") (pintype "unspecified"))
      (node (ref "J9") (pin "80") (pinfunction "80_80") (pintype "unspecified"))
    )
    (net (code "201") (name "SOCKET_81") (class "Default")
      (node (ref "J8") (pin "82") (pinfunction "MD9_82") (pintype "unspecified"))
      (node (ref "J9") (pin "81") (pinfunction "81_81") (pintype "unspecified"))
    )
    (net (code "202") (name "SOCKET_82") (class "Default")
      (node (ref "J8") (pin "81") (pinfunction "MD8_81") (pintype "unspecified"))
      (node (ref "J9") (pin "82") (pinfunction "82_82") (pintype "unspecified"))
    )
    (net (code "203") (name "SOCKET_83") (class "Default")
      (node (ref "J8") (pin "84") (pinfunction "MD11_84") (pintype "unspecified"))
      (node (ref "J9") (pin "83") (pinfunction "83_83") (pintype "unspecified"))
    )
    (net (code "204") (name "SOCKET_84") (class "Default")
      (node (ref "J8") (pin "83") (pinfunction "MD10_83") (pintype "unspecified"))
      (node (ref "J9") (pin "84") (pinfunction "84_84") (pintype "unspecified"))
    )
    (net (code "205") (name "SOCKET_85") (class "Default")
      (node (ref "J8") (pin "86") (pinfunction "MD13_86") (pintype "unspecified"))
      (node (ref "J9") (pin "85") (pinfunction "85_85") (pintype "unspecified"))
    )
    (net (code "206") (name "SOCKET_86") (class "Default")
      (node (ref "J8") (pin "85") (pinfunction "MD12_85") (pintype "unspecified"))
      (node (ref "J9") (pin "86") (pinfunction "86_86") (pintype "unspecified"))
    )
    (net (code "207") (name "SOCKET_87") (class "Default")
      (node (ref "J8") (pin "88") (pinfunction "MD15_88") (pintype "unspecified"))
      (node (ref "J9") (pin "87") (pinfunction "87_87") (pintype "unspecified"))
    )
    (net (code "208") (name "SOCKET_88") (class "Default")
      (node (ref "J8") (pin "87") (pinfunction "MD14_87") (pintype "unspecified"))
      (node (ref "J9") (pin "88") (pinfunction "88_88") (pintype "unspecified"))
    )
    (net (code "209") (name "SOCKET_89") (class "Default")
      (node (ref "J8") (pin "90") (pinfunction "DGND_90") (pintype "unspecified"))
      (node (ref "J9") (pin "89") (pinfunction "89_89") (pintype "unspecified"))
    )
    (net (code "210") (name "SOCKET_90") (class "Default")
      (node (ref "J8") (pin "89") (pinfunction "DGND_89") (pintype "unspecified"))
      (node (ref "J9") (pin "90") (pinfunction "90_90") (pintype "unspecified"))
    )
    (net (code "211") (name "SOCKET_91") (class "Default")
      (node (ref "J8") (pin "92") (pinfunction "+5V_92") (pintype "unspecified"))
      (node (ref "J9") (pin "91") (pinfunction "91_91") (pintype "unspecified"))
    )
    (net (code "212") (name "SOCKET_92") (class "Default")
      (node (ref "J8") (pin "91") (pinfunction "+5V_91") (pintype "unspecified"))
      (node (ref "J9") (pin "92") (pinfunction "92_92") (pintype "unspecified"))
    )
    (net (code "213") (name "SOCKET_93") (class "Default")
      (node (ref "J8") (pin "94") (pinfunction "RA2_94") (pintype "unspecified"))
      (node (ref "J9") (pin "93") (pinfunction "93_93") (pintype "unspecified"))
    )
    (net (code "214") (name "SOCKET_94") (class "Default")
      (node (ref "J8") (pin "93") (pinfunction "RA1_93") (pintype "unspecified"))
      (node (ref "J9") (pin "94") (pinfunction "94_94") (pintype "unspecified"))
    )
    (net (code "215") (name "SOCKET_95") (class "Default")
      (node (ref "J8") (pin "96") (pinfunction "RA4_96") (pintype "unspecified"))
      (node (ref "J9") (pin "95") (pinfunction "95_95") (pintype "unspecified"))
    )
    (net (code "216") (name "SOCKET_96") (class "Default")
      (node (ref "J8") (pin "95") (pinfunction "RA3_95") (pintype "unspecified"))
      (node (ref "J9") (pin "96") (pinfunction "96_96") (pintype "unspecified"))
    )
    (net (code "217") (name "SOCKET_97") (class "Default")
      (node (ref "J8") (pin "98") (pinfunction "RA6_98") (pintype "unspecified"))
      (node (ref "J9") (pin "97") (pinfunction "97_97") (pintype "unspecified"))
    )
    (net (code "218") (name "SOCKET_98") (class "Default")
      (node (ref "J8") (pin "97") (pinfunction "RA5_97") (pintype "unspecified"))
      (node (ref "J9") (pin "98") (pinfunction "98_98") (pintype "unspecified"))
    )
    (net (code "219") (name "SOCKET_99") (class "Default")
      (node (ref "J8") (pin "100") (pinfunction "RA8_100") (pintype "unspecified"))
      (node (ref "J9") (pin "99") (pinfunction "99_99") (pintype "unspecified"))
    )
    (net (code "220") (name "SOCKET_100") (class "Default")
      (node (ref "J8") (pin "99") (pinfunction "RA7_99") (pintype "unspecified"))
      (node (ref "J9") (pin "100") (pinfunction "100_100") (pintype "unspecified"))
    )
    (net (code "221") (name "SOCKET_101") (class "Default")
      (node (ref "J8") (pin "102") (pinfunction "A16_102") (pintype "unspecified"))
      (node (ref "J9") (pin "101") (pinfunction "101_101") (pintype "unspecified"))
    )
    (net (code "222") (name "SOCKET_102") (class "Default")
      (node (ref "J8") (pin "101") (pinfunction "/RSTSW_101") (pintype "unspecified"))
      (node (ref "J9") (pin "102") (pinfunction "102_102") (pintype "unspecified"))
    )
    (net (code "223") (name "SOCKET_103") (class "Default")
      (node (ref "J8") (pin "104") (pinfunction "A18_104") (pintype "unspecified"))
      (node (ref "J9") (pin "103") (pinfunction "103_103") (pintype "unspecified"))
    )
    (net (code "224") (name "SOCKET_104") (class "Default")
      (node (ref "J8") (pin "103") (pinfunction "A17_103") (pintype "unspecified"))
      (node (ref "J9") (pin "104") (pinfunction "104_104") (pintype "unspecified"))
    )
    (net (code "225") (name "SOCKET_105") (class "Default")
      (node (ref "J8") (pin "106") (pinfunction "DOTCK_106") (pintype "unspecified"))
      (node (ref "J9") (pin "105") (pinfunction "105_105") (pintype "unspecified"))
    )
    (net (code "226") (name "SOCKET_106") (class "Default")
      (node (ref "J8") (pin "105") (pinfunction "A19_105") (pintype "unspecified"))
      (node (ref "J9") (pin "106") (pinfunction "106_106") (pintype "unspecified"))
    )
    (net (code "227") (name "SOCKET_107") (class "Default")
      (node (ref "J8") (pin "108") (pinfunction "/CAS_108") (pintype "unspecified"))
      (node (ref "J9") (pin "107") (pinfunction "107_107") (pintype "unspecified"))
    )
    (net (code "228") (name "SOCKET_108") (class "Default")
      (node (ref "J8") (pin "107") (pinfunction "MREAD_107") (pintype "unspecified"))
      (node (ref "J9") (pin "108") (pinfunction "108_108") (pintype "unspecified"))
    )
    (net (code "229") (name "SOCKET_109") (class "Default")
      (node (ref "J8") (pin "110") (pinfunction "A20_110") (pintype "unspecified"))
      (node (ref "J9") (pin "109") (pinfunction "109_109") (pintype "unspecified"))
    )
    (net (code "230") (name "SOCKET_110") (class "Default")
      (node (ref "J8") (pin "109") (pinfunction "/RAS_109") (pintype "unspecified"))
      (node (ref "J9") (pin "110") (pinfunction "110_110") (pintype "unspecified"))
    )
    (net (code "231") (name "SOCKET_111") (class "Default")
      (node (ref "J8") (pin "112") (pinfunction "/HDER_112") (pintype "unspecified"))
      (node (ref "J9") (pin "111") (pinfunction "111_111") (pintype "unspecified"))
    )
    (net (code "232") (name "SOCKET_112") (class "Default")
      (node (ref "J8") (pin "111") (pinfunction "/HSYNC_111") (pintype "unspecified"))
      (node (ref "J9") (pin "112") (pinfunction "112_112") (pintype "unspecified"))
    )
    (net (code "233") (name "SOCKET_113") (class "Default")
      (node (ref "J8") (pin "114") (pinfunction "/SFER_114") (pintype "unspecified"))
      (node (ref "J9") (pin "113") (pinfunction "113_113") (pintype "unspecified"))
    )
    (net (code "234") (name "SOCKET_114") (class "Default")
      (node (ref "J8") (pin "113") (pinfunction "/VSYNC_113") (pintype "unspecified"))
      (node (ref "J9") (pin "114") (pinfunction "114_114") (pintype "unspecified"))
    )
    (net (code "235") (name "SOCKET_115") (class "Default")
      (node (ref "J8") (pin "116") (pinfunction "/NMI_116") (pintype "unspecified"))
      (node (ref "J9") (pin "115") (pinfunction "115_115") (pintype "unspecified"))
    )
    (net (code "236") (name "SOCKET_116") (class "Default")
      (node (ref "J8") (pin "115") (pinfunction "VID_115") (pintype "unspecified"))
      (node (ref "J9") (pin "116") (pinfunction "116_116") (pintype "unspecified"))
    )
    (net (code "237") (name "SOCKET_117") (class "Default")
      (node (ref "J8") (pin "118") (pinfunction "DGND_118") (pintype "unspecified"))
      (node (ref "J9") (pin "117") (pinfunction "117_117") (pintype "unspecified"))
    )
    (net (code "238") (name "SOCKET_118") (class "Default")
      (node (ref "J8") (pin "117") (pinfunction "DGND_117") (pintype "unspecified"))
      (node (ref "J9") (pin "118") (pinfunction "118_118") (pintype "unspecified"))
    )
    (net (code "239") (name "SOCKET_119") (class "Default")
      (node (ref "J8") (pin "120") (pinfunction "+5V_120") (pintype "unspecified"))
      (node (ref "J9") (pin "119") (pinfunction "119_119") (pintype "unspecified"))
    )
    (net (code "240") (name "SOCKET_120") (class "Default")
      (node (ref "J8") (pin "119") (pinfunction "+5V_119") (pintype "unspecified"))
      (node (ref "J9") (pin "120") (pinfunction "120_120") (pintype "unspecified"))
    )
  )
)
